# dnt_mko.net
KiCad netlist of a schematic drawn in Altium Designer
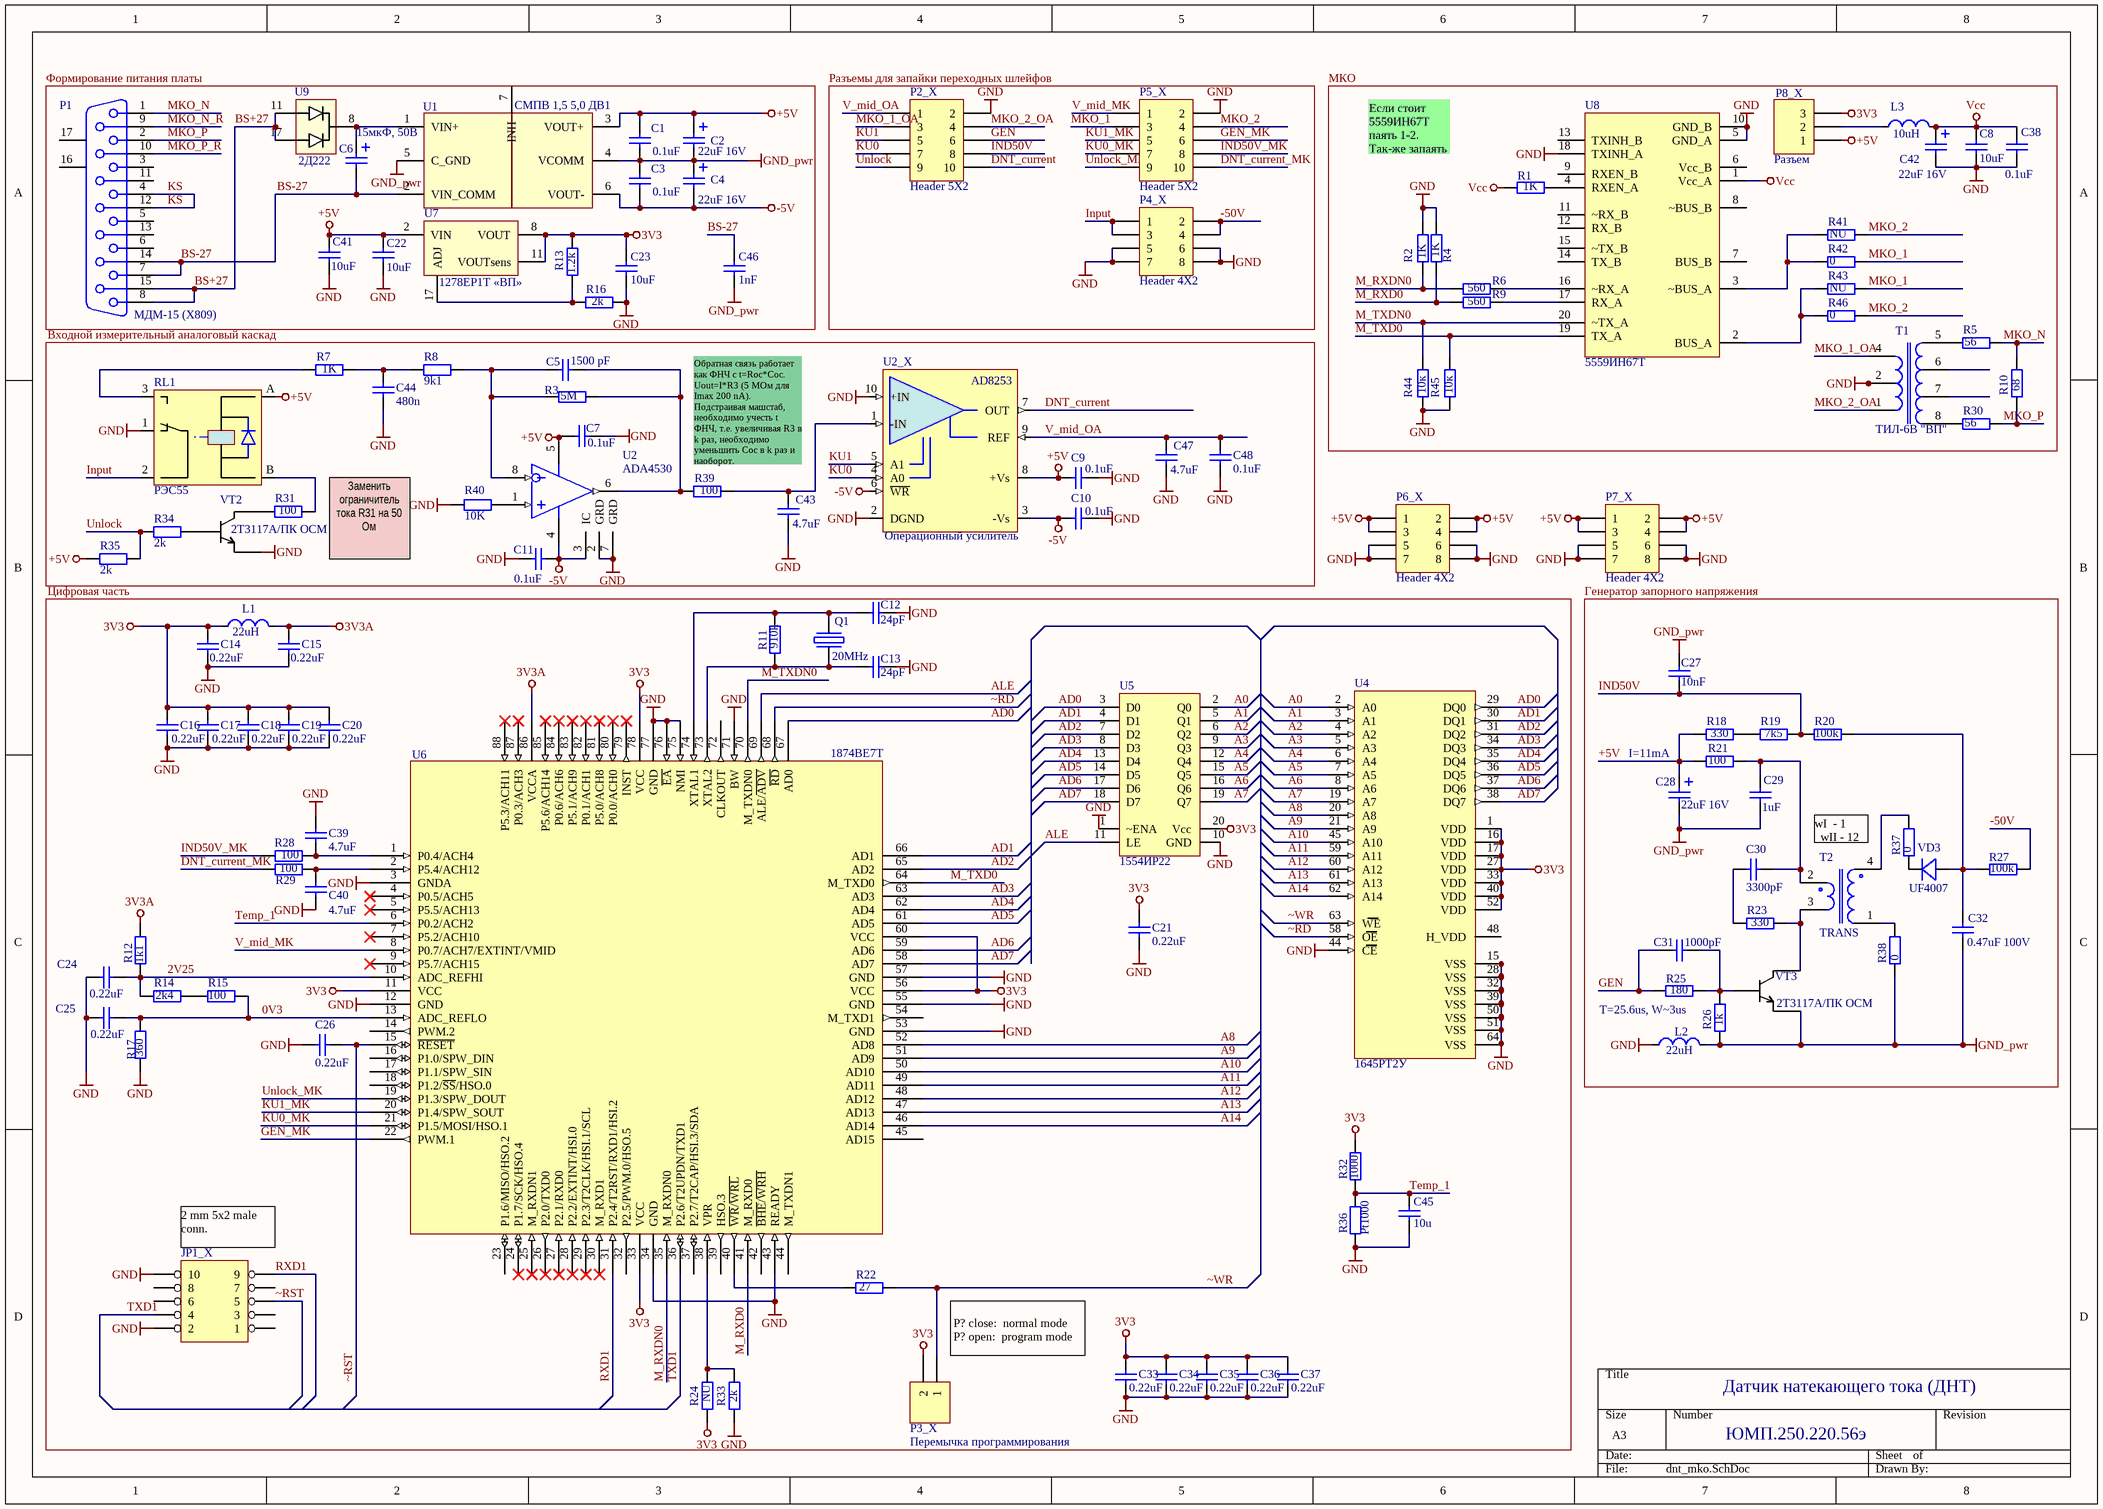
[diagram p0: dnt_mko.SchDoc]

(export (version "E")
  (design (tool "Eeschema 10.0.6"))
  (components
    (comp (ref "C1")
      (value "0.1uF")
      (footprint "CR-0805")
      (description "Capacitor")
      (fields (field (name "PUBLISHER") "Altium Limited"))
      (libsource (lib "MyLib") (part "C"))
    )
    (comp (ref "C2")
      (value "22uF 16V")
      (footprint "C_SMD_SIZE_B")
      (description "Capacitor")
      (fields (field (name "PUBLISHER") "Altium Limited"))
      (libsource (lib "MyLib") (part "C_pol"))
    )
    (comp (ref "C3")
      (value "0.1uF")
      (footprint "CR-0805")
      (description "Capacitor")
      (fields (field (name "PUBLISHER") "Altium Limited"))
      (libsource (lib "MyLib") (part "C"))
    )
    (comp (ref "C4")
      (value "22uF 16V")
      (footprint "C_SMD_SIZE_B")
      (description "Capacitor")
      (fields (field (name "PUBLISHER") "Altium Limited"))
      (libsource (lib "MyLib") (part "C_pol"))
    )
    (comp (ref "C5")
      (value "1500 pF")
      (footprint "CR-0805")
      (description "Capacitor")
      (fields (field (name "PUBLISHER") "Altium Limited"))
      (libsource (lib "MyLib") (part "C"))
    )
    (comp (ref "C6")
      (value "15мкФ, 50В")
      (footprint "C_SMD_size_D")
      (description "Capacitor")
      (fields (field (name "PUBLISHER") "Altium Limited"))
      (libsource (lib "MyLib") (part "C_pol"))
    )
    (comp (ref "C7")
      (value "0.1uF")
      (footprint "CR-0805")
      (description "Capacitor")
      (fields (field (name "PUBLISHER") "Altium Limited"))
      (libsource (lib "MyLib") (part "C"))
    )
    (comp (ref "C8")
      (value "10uF")
      (footprint "CR-0805")
      (description "Capacitor")
      (fields (field (name "PUBLISHER") "Altium Limited"))
      (libsource (lib "MyLib") (part "C"))
    )
    (comp (ref "C9")
      (value "0.1uF")
      (footprint "CR-0805")
      (description "Capacitor")
      (fields (field (name "PUBLISHER") "Altium Limited"))
      (libsource (lib "MyLib") (part "C"))
    )
    (comp (ref "C10")
      (value "0.1uF")
      (footprint "CR-0805")
      (description "Capacitor")
      (fields (field (name "PUBLISHER") "Altium Limited"))
      (libsource (lib "MyLib") (part "C"))
    )
    (comp (ref "C11")
      (value "0.1uF")
      (footprint "CR-0805")
      (description "Capacitor")
      (fields (field (name "PUBLISHER") "Altium Limited"))
      (libsource (lib "MyLib") (part "C"))
    )
    (comp (ref "C12")
      (value "24pF")
      (footprint "CR-0805")
      (description "Capacitor")
      (fields (field (name "PUBLISHER") "Altium Limited"))
      (libsource (lib "MyLib") (part "C"))
    )
    (comp (ref "C13")
      (value "24pF")
      (footprint "CR-0805")
      (description "Capacitor")
      (fields (field (name "PUBLISHER") "Altium Limited"))
      (libsource (lib "MyLib") (part "C"))
    )
    (comp (ref "C14")
      (value "0.22uF")
      (footprint "CR-0805")
      (description "Capacitor")
      (fields (field (name "PUBLISHER") "Altium Limited"))
      (libsource (lib "MyLib") (part "C"))
    )
    (comp (ref "C15")
      (value "0.22uF")
      (footprint "CR-0805")
      (description "Capacitor")
      (fields (field (name "PUBLISHER") "Altium Limited"))
      (libsource (lib "MyLib") (part "C"))
    )
    (comp (ref "C16")
      (value "0.22uF")
      (footprint "CR-0805")
      (description "Capacitor")
      (fields (field (name "PUBLISHER") "Altium Limited"))
      (libsource (lib "MyLib") (part "C"))
    )
    (comp (ref "C17")
      (value "0.22uF")
      (footprint "CR-0805")
      (description "Capacitor")
      (fields (field (name "PUBLISHER") "Altium Limited"))
      (libsource (lib "MyLib") (part "C"))
    )
    (comp (ref "C18")
      (value "0.22uF")
      (footprint "CR-0805")
      (description "Capacitor")
      (fields (field (name "PUBLISHER") "Altium Limited"))
      (libsource (lib "MyLib") (part "C"))
    )
    (comp (ref "C19")
      (value "0.22uF")
      (footprint "CR-0805")
      (description "Capacitor")
      (fields (field (name "PUBLISHER") "Altium Limited"))
      (libsource (lib "MyLib") (part "C"))
    )
    (comp (ref "C20")
      (value "0.22uF")
      (footprint "CR-0805")
      (description "Capacitor")
      (fields (field (name "PUBLISHER") "Altium Limited"))
      (libsource (lib "MyLib") (part "C"))
    )
    (comp (ref "C21")
      (value "0.22uF")
      (footprint "CR-0805")
      (description "Capacitor")
      (fields (field (name "PUBLISHER") "Altium Limited"))
      (libsource (lib "MyLib") (part "C"))
    )
    (comp (ref "C22")
      (value "10uF")
      (footprint "CR-0805")
      (description "Capacitor")
      (fields (field (name "PUBLISHER") "Altium Limited"))
      (libsource (lib "MyLib") (part "C"))
    )
    (comp (ref "C23")
      (value "10uF")
      (footprint "CR-0805")
      (description "Capacitor")
      (fields (field (name "PUBLISHER") "Altium Limited"))
      (libsource (lib "MyLib") (part "C"))
    )
    (comp (ref "C24")
      (value "0.22uF")
      (footprint "CR-0805")
      (description "Capacitor")
      (fields (field (name "PUBLISHER") "Altium Limited"))
      (libsource (lib "MyLib") (part "C"))
    )
    (comp (ref "C25")
      (value "0.22uF")
      (footprint "CR-0805")
      (description "Capacitor")
      (fields (field (name "PUBLISHER") "Altium Limited"))
      (libsource (lib "MyLib") (part "C"))
    )
    (comp (ref "C26")
      (value "0.22uF")
      (footprint "CR-0805")
      (description "Capacitor")
      (fields (field (name "PUBLISHER") "Altium Limited"))
      (libsource (lib "MyLib") (part "C"))
    )
    (comp (ref "C27")
      (value "10nF")
      (footprint "CR-0805")
      (description "Capacitor")
      (fields (field (name "PUBLISHER") "Altium Limited"))
      (libsource (lib "MyLib") (part "C"))
    )
    (comp (ref "C28")
      (value "22uF 16V")
      (footprint "C_SMD_SIZE_B")
      (description "Capacitor")
      (fields (field (name "PUBLISHER") "Altium Limited"))
      (libsource (lib "MyLib") (part "C_pol"))
    )
    (comp (ref "C29")
      (value "1uF")
      (footprint "CR-0805")
      (description "Capacitor")
      (fields (field (name "PUBLISHER") "Altium Limited"))
      (libsource (lib "MyLib") (part "C"))
    )
    (comp (ref "C30")
      (value "3300pF")
      (footprint "CR-0805")
      (description "Capacitor")
      (fields (field (name "PUBLISHER") "Altium Limited"))
      (libsource (lib "MyLib") (part "C"))
    )
    (comp (ref "C31")
      (value "1000pF")
      (footprint "CR-0805")
      (description "Capacitor")
      (fields (field (name "PUBLISHER") "Altium Limited"))
      (libsource (lib "MyLib") (part "C"))
    )
    (comp (ref "C32")
      (value "0.47uF 100V")
      (footprint "CR-0805")
      (description "Capacitor")
      (fields (field (name "PUBLISHER") "Altium Limited"))
      (libsource (lib "MyLib") (part "C"))
    )
    (comp (ref "C33")
      (value "0.22uF")
      (footprint "CR-0805")
      (description "Capacitor")
      (fields (field (name "PUBLISHER") "Altium Limited"))
      (libsource (lib "MyLib") (part "C"))
    )
    (comp (ref "C34")
      (value "0.22uF")
      (footprint "CR-0805")
      (description "Capacitor")
      (fields (field (name "PUBLISHER") "Altium Limited"))
      (libsource (lib "MyLib") (part "C"))
    )
    (comp (ref "C35")
      (value "0.22uF")
      (footprint "CR-0805")
      (description "Capacitor")
      (fields (field (name "PUBLISHER") "Altium Limited"))
      (libsource (lib "MyLib") (part "C"))
    )
    (comp (ref "C36")
      (value "0.22uF")
      (footprint "CR-0805")
      (description "Capacitor")
      (fields (field (name "PUBLISHER") "Altium Limited"))
      (libsource (lib "MyLib") (part "C"))
    )
    (comp (ref "C37")
      (value "0.22uF")
      (footprint "CR-0805")
      (description "Capacitor")
      (fields (field (name "PUBLISHER") "Altium Limited"))
      (libsource (lib "MyLib") (part "C"))
    )
    (comp (ref "C38")
      (value "0.1uF")
      (footprint "CR-0805")
      (description "Capacitor")
      (fields (field (name "PUBLISHER") "Altium Limited"))
      (libsource (lib "MyLib") (part "C"))
    )
    (comp (ref "C39")
      (value "4.7uF")
      (footprint "CR-0805")
      (description "Capacitor")
      (fields (field (name "PUBLISHER") "Altium Limited"))
      (libsource (lib "MyLib") (part "C"))
    )
    (comp (ref "C40")
      (value "4.7uF")
      (footprint "CR-0805")
      (description "Capacitor")
      (fields (field (name "PUBLISHER") "Altium Limited"))
      (libsource (lib "MyLib") (part "C"))
    )
    (comp (ref "C41")
      (value "10uF")
      (footprint "CR-0805")
      (description "Capacitor")
      (fields (field (name "PUBLISHER") "Altium Limited"))
      (libsource (lib "MyLib") (part "C"))
    )
    (comp (ref "C42")
      (value "22uF 16V")
      (footprint "C_SMD_SIZE_B")
      (description "Capacitor")
      (fields (field (name "PUBLISHER") "Altium Limited"))
      (libsource (lib "MyLib") (part "C_pol"))
    )
    (comp (ref "C43")
      (value "4.7uF")
      (footprint "CR-0805")
      (description "Capacitor")
      (fields (field (name "PUBLISHER") "Altium Limited"))
      (libsource (lib "MyLib") (part "C"))
    )
    (comp (ref "C44")
      (value "480n")
      (footprint "CR-0805")
      (description "Capacitor")
      (fields (field (name "PUBLISHER") "Altium Limited"))
      (libsource (lib "MyLib") (part "C"))
    )
    (comp (ref "C45")
      (value "10u")
      (footprint "CR-0805")
      (description "Capacitor")
      (fields (field (name "PUBLISHER") "Altium Limited"))
      (libsource (lib "MyLib") (part "C"))
    )
    (comp (ref "C46")
      (value "1nF")
      (footprint "CR-1206")
      (description "Capacitor")
      (fields (field (name "PUBLISHER") "Altium Limited"))
      (libsource (lib "MyLib") (part "C"))
    )
    (comp (ref "C47")
      (value "4.7uF")
      (footprint "CR-0805")
      (description "Capacitor")
      (fields (field (name "PUBLISHER") "Altium Limited"))
      (libsource (lib "MyLib") (part "C"))
    )
    (comp (ref "C48")
      (value "0.1uF")
      (footprint "CR-0805")
      (description "Capacitor")
      (fields (field (name "PUBLISHER") "Altium Limited"))
      (libsource (lib "MyLib") (part "C"))
    )
    (comp (ref "JP1_X") (value "~") (footprint "IDC2-10") (libsource (lib "*") (part "HEADER 5X2")))
    (comp (ref "L1")
      (value "22uH")
      (footprint "C_SMD_SIZE_B")
      (description "Inductor")
      (libsource (lib "*") (part "INDUCTOR"))
    )
    (comp (ref "L2")
      (value "22uH")
      (footprint "C_SMD_SIZE_B")
      (description "Inductor")
      (libsource (lib "*") (part "INDUCTOR"))
    )
    (comp (ref "L3")
      (value "10uH")
      (footprint "C_SMD_SIZE_B")
      (description "Inductor")
      (libsource (lib "*") (part "INDUCTOR"))
    )
    (comp (ref "P1")
      (value "MDM-15")
      (footprint "MDM-15")
      (description "Receptacle Assembly, 15 Position, Right Angle")
      (fields (field (name "НАИМЕНОВАНИЕ") "МДМ-15 (X809)"))
      (libsource (lib "Miscellaneous Connectors") (part "D Connector 15"))
    )
    (comp (ref "P2_X")
      (value "Header 5X2")
      (footprint "IDC2-10")
      (description "Header, 5-Pin, Dual row")
      (fields (field (name "PUBLISHER") "Altium Limited"))
      (libsource (lib "Miscellaneous Connectors") (part "Header 5X2"))
    )
    (comp (ref "P3_X")
      (value "Перемычка программирования")
      (footprint "IDC2-2")
      (description "Header, 2-Pin")
      (libsource (lib "Miscellaneous Connectors") (part "Header 2"))
    )
    (comp (ref "P4_X")
      (value "Header 4X2")
      (footprint "IDC2-8")
      (description "Header, 4-Pin, Dual row")
      (fields (field (name "PUBLISHER") "Altium Limited"))
      (libsource (lib "Miscellaneous Connectors") (part "Header 4X2"))
    )
    (comp (ref "P5_X")
      (value "Header 5X2")
      (footprint "IDC2-10")
      (description "Header, 5-Pin, Dual row")
      (fields (field (name "PUBLISHER") "Altium Limited"))
      (libsource (lib "Miscellaneous Connectors") (part "Header 5X2"))
    )
    (comp (ref "P6_X")
      (value "Header 4X2")
      (footprint "IDC2-8")
      (description "Header, 4-Pin, Dual row")
      (fields (field (name "PUBLISHER") "Altium Limited"))
      (libsource (lib "Miscellaneous Connectors") (part "Header 4X2"))
    )
    (comp (ref "P7_X")
      (value "Header 4X2")
      (footprint "IDC2-8")
      (description "Header, 4-Pin, Dual row")
      (fields (field (name "PUBLISHER") "Altium Limited"))
      (libsource (lib "Miscellaneous Connectors") (part "Header 4X2"))
    )
    (comp (ref "P8_X")
      (value "Разъем")
      (footprint "IDC2-3")
      (description "Header, 3-Pin")
      (fields (field (name "PUBLISHER") "Altium Limited"))
      (libsource (lib "Miscellaneous Connectors") (part "Header 3"))
    )
    (comp (ref "Q1")
      (value "20MHz")
      (footprint "RK-386MM")
      (description "Resonator")
      (libsource (lib "*") (part "QUARZ"))
    )
    (comp (ref "R1")
      (value "1K")
      (footprint "CR-0805")
      (description "Resistor")
      (fields (field (name "PUBLISHER") "Altium Limited"))
      (libsource (lib "MyLib") (part "R"))
    )
    (comp (ref "R2")
      (value "1K")
      (footprint "CR-0805")
      (description "Resistor")
      (fields (field (name "PUBLISHER") "Altium Limited"))
      (libsource (lib "") (part "R_2"))
    )
    (comp (ref "R3")
      (value "5M")
      (footprint "CR-1206")
      (description "Resistor")
      (libsource (lib "") (part "R_1"))
    )
    (comp (ref "R4")
      (value "1K")
      (footprint "CR-0805")
      (description "Resistor")
      (fields (field (name "PUBLISHER") "Altium Limited"))
      (libsource (lib "") (part "R_2"))
    )
    (comp (ref "R5")
      (value "56")
      (footprint "CR-1206")
      (description "Resistor")
      (fields (field (name "PUBLISHER") "Altium Limited"))
      (libsource (lib "") (part "R_1"))
    )
    (comp (ref "R6")
      (value "560")
      (footprint "CR-0805")
      (description "Resistor")
      (fields (field (name "PUBLISHER") "Altium Limited"))
      (libsource (lib "") (part "R_1"))
    )
    (comp (ref "R7")
      (value "1K")
      (footprint "CR-0805")
      (description "Resistor")
      (fields (field (name "PUBLISHER") "Altium Limited"))
      (libsource (lib "MyLib") (part "R"))
    )
    (comp (ref "R8")
      (value "9k1")
      (footprint "CR-0805")
      (description "Resistor")
      (fields (field (name "PUBLISHER") "Altium Limited"))
      (libsource (lib "") (part "R_1"))
    )
    (comp (ref "R9")
      (value "560")
      (footprint "CR-0805")
      (description "Resistor")
      (fields (field (name "PUBLISHER") "Altium Limited"))
      (libsource (lib "") (part "R_1"))
    )
    (comp (ref "R10")
      (value "68")
      (footprint "CR-1206")
      (description "Resistor")
      (fields (field (name "PUBLISHER") "Altium Limited"))
      (libsource (lib "") (part "R_3"))
    )
    (comp (ref "R11")
      (value "910k")
      (footprint "CR-0805")
      (description "Resistor")
      (fields (field (name "PUBLISHER") "Altium Limited"))
      (libsource (lib "") (part "R_3"))
    )
    (comp (ref "R12")
      (value "1k1")
      (footprint "CR-0805")
      (description "Resistor")
      (fields (field (name "PUBLISHER") "Altium Limited"))
      (libsource (lib "") (part "R_2"))
    )
    (comp (ref "R13")
      (value "1.2k")
      (footprint "CR-0805")
      (description "Resistor")
      (fields (field (name "PUBLISHER") "Altium Limited"))
      (libsource (lib "") (part "R_2"))
    )
    (comp (ref "R14")
      (value "2k4")
      (footprint "CR-0805")
      (description "Resistor")
      (fields (field (name "PUBLISHER") "Altium Limited"))
      (libsource (lib "") (part "R_1"))
    )
    (comp (ref "R15")
      (value "100")
      (footprint "CR-0805")
      (description "Resistor")
      (fields (field (name "PUBLISHER") "Altium Limited"))
      (libsource (lib "") (part "R_1"))
    )
    (comp (ref "R16")
      (value "2k")
      (footprint "CR-0805")
      (description "Resistor")
      (fields (field (name "PUBLISHER") "Altium Limited"))
      (libsource (lib "MyLib") (part "R"))
    )
    (comp (ref "R17")
      (value "360")
      (footprint "CR-0805")
      (description "Resistor")
      (fields (field (name "PUBLISHER") "Altium Limited"))
      (libsource (lib "") (part "R_2"))
    )
    (comp (ref "R18")
      (value "330")
      (footprint "CR-0805")
      (description "Resistor")
      (fields (field (name "PUBLISHER") "Altium Limited"))
      (libsource (lib "") (part "R_1"))
    )
    (comp (ref "R19")
      (value "7k5")
      (footprint "CR-0805")
      (description "Resistor")
      (fields (field (name "PUBLISHER") "Altium Limited"))
      (libsource (lib "") (part "R_1"))
    )
    (comp (ref "R20")
      (value "100k")
      (footprint "CR-0805")
      (description "Resistor")
      (fields (field (name "PUBLISHER") "Altium Limited"))
      (libsource (lib "") (part "R_1"))
    )
    (comp (ref "R21")
      (value "100")
      (footprint "CR-0805")
      (description "Resistor")
      (fields (field (name "PUBLISHER") "Altium Limited"))
      (libsource (lib "") (part "R_1"))
    )
    (comp (ref "R22")
      (value "27")
      (footprint "CR-0805")
      (description "Resistor")
      (fields (field (name "PUBLISHER") "Altium Limited"))
      (libsource (lib "") (part "R_1"))
    )
    (comp (ref "R23")
      (value "330")
      (footprint "CR-0805")
      (description "Resistor")
      (fields (field (name "PUBLISHER") "Altium Limited"))
      (libsource (lib "") (part "R_1"))
    )
    (comp (ref "R24")
      (value "NU")
      (footprint "CR-0805")
      (description "Resistor")
      (fields (field (name "PUBLISHER") "Altium Limited"))
      (libsource (lib "") (part "R_3"))
    )
    (comp (ref "R25")
      (value "180")
      (footprint "CR-0805")
      (description "Resistor")
      (fields (field (name "PUBLISHER") "Altium Limited"))
      (libsource (lib "") (part "R_1"))
    )
    (comp (ref "R26")
      (value "1k")
      (footprint "CR-0805")
      (description "Resistor")
      (fields (field (name "PUBLISHER") "Altium Limited"))
      (libsource (lib "") (part "R_3"))
    )
    (comp (ref "R27")
      (value "100k")
      (footprint "CR-0805")
      (description "Resistor")
      (fields (field (name "PUBLISHER") "Altium Limited"))
      (libsource (lib "MyLib") (part "R"))
    )
    (comp (ref "R28")
      (value "100")
      (footprint "CR-0805")
      (description "Resistor")
      (fields (field (name "PUBLISHER") "Altium Limited"))
      (libsource (lib "") (part "R_1"))
    )
    (comp (ref "R29")
      (value "100")
      (footprint "CR-0805")
      (description "Resistor")
      (fields (field (name "PUBLISHER") "Altium Limited"))
      (libsource (lib "") (part "R_1"))
    )
    (comp (ref "R30")
      (value "56")
      (footprint "CR-1206")
      (description "Resistor")
      (fields (field (name "PUBLISHER") "Altium Limited"))
      (libsource (lib "") (part "R_1"))
    )
    (comp (ref "R31")
      (value "100")
      (footprint "CR-0805")
      (description "Resistor")
      (fields (field (name "PUBLISHER") "Altium Limited"))
      (libsource (lib "MyLib") (part "R"))
    )
    (comp (ref "R32")
      (value "1000")
      (footprint "CR-0805")
      (description "Resistor")
      (fields (field (name "PUBLISHER") "Altium Limited"))
      (libsource (lib "") (part "R_3"))
    )
    (comp (ref "R33")
      (value "2k")
      (footprint "CR-0805")
      (description "Resistor")
      (fields (field (name "PUBLISHER") "Altium Limited"))
      (libsource (lib "") (part "R_3"))
    )
    (comp (ref "R34")
      (value "2k")
      (footprint "CR-0805")
      (description "Resistor")
      (fields (field (name "PUBLISHER") "Altium Limited"))
      (libsource (lib "MyLib") (part "R"))
    )
    (comp (ref "R35")
      (value "2k")
      (footprint "CR-0805")
      (description "Resistor")
      (fields (field (name "PUBLISHER") "Altium Limited"))
      (libsource (lib "") (part "R_1"))
    )
    (comp (ref "R36")
      (value "Pt1000")
      (footprint "Pt100")
      (description "Resistor")
      (fields (field (name "PUBLISHER") "Altium Limited"))
      (libsource (lib "") (part "R_3"))
    )
    (comp (ref "R37")
      (value "0")
      (footprint "CR-0805")
      (description "Resistor")
      (fields (field (name "PUBLISHER") "Altium Limited"))
      (libsource (lib "") (part "R_3"))
    )
    (comp (ref "R38")
      (value "0")
      (footprint "CR-0805")
      (description "Resistor")
      (fields (field (name "PUBLISHER") "Altium Limited"))
      (libsource (lib "") (part "R_3"))
    )
    (comp (ref "R39")
      (value "100")
      (footprint "CR-0805")
      (description "Resistor")
      (fields (field (name "PUBLISHER") "Altium Limited"))
      (libsource (lib "MyLib") (part "R"))
    )
    (comp (ref "R40")
      (value "10K")
      (footprint "CR-0805")
      (description "Resistor")
      (fields (field (name "PUBLISHER") "Altium Limited"))
      (libsource (lib "MyLib") (part "R"))
    )
    (comp (ref "R41")
      (value "NU")
      (footprint "CR-0805")
      (description "Resistor")
      (fields (field (name "PUBLISHER") "Altium Limited"))
      (libsource (lib "") (part "R_1"))
    )
    (comp (ref "R42")
      (value "0")
      (footprint "CR-0805")
      (description "Resistor")
      (fields (field (name "PUBLISHER") "Altium Limited"))
      (libsource (lib "") (part "R_1"))
    )
    (comp (ref "R43")
      (value "NU")
      (footprint "CR-0805")
      (description "Resistor")
      (fields (field (name "PUBLISHER") "Altium Limited"))
      (libsource (lib "") (part "R_1"))
    )
    (comp (ref "R44")
      (value "10к")
      (footprint "CR-0805")
      (description "Resistor")
      (fields (field (name "PUBLISHER") "Altium Limited"))
      (libsource (lib "") (part "R_2"))
    )
    (comp (ref "R45")
      (value "10к")
      (footprint "CR-0805")
      (description "Resistor")
      (fields (field (name "PUBLISHER") "Altium Limited"))
      (libsource (lib "") (part "R_2"))
    )
    (comp (ref "R46")
      (value "0")
      (footprint "CR-0805")
      (description "Resistor")
      (fields (field (name "PUBLISHER") "Altium Limited"))
      (libsource (lib "") (part "R_1"))
    )
    (comp (ref "RL1")
      (value "РЭС55")
      (footprint "MyLib_1:РЭС55")
      (description "Реле")
      (libsource (lib "MyLib") (part "RGK-56"))
    )
    (comp (ref "T1")
      (value "ТИЛ-6В \"ВП\"")
      (footprint "ТИЛ6В")
      (description "Transformator")
      (libsource (lib "*") (part "TIL6B"))
    )
    (comp (ref "T2")
      (value "TRANS")
      (footprint "TRANS 50V")
      (description "Transformer")
      (libsource (lib "My_lib_1") (part "TRANS"))
    )
    (comp (ref "U1")
      (value "СМПВ 1,5 5,0 ДВ1")
      (footprint "SLH 2805")
      (libsource (lib "My_lib_1") (part "SLH2805"))
    )
    (comp (ref "U2")
      (value "ADA4530")
      (footprint "MyLib:SO-8")
      (description "Ultra-Low Bias Current Difet OpAmp")
      (libsource (lib "My_lib_1") (part "ADA4530"))
    )
    (comp (ref "U2_X")
      (value "AD8253")
      (footprint "u_SO-10")
      (description "10 MHz, 20 V/мs, G = 1, 2, 4, 8 iCMOS Programmable Gain Instrumentation Amplifier")
      (fields (field (name "НАЗНАЧЕНИЕ") "Операционный усилитель") (field (name "НАИМЕНОВАНИЕ") "AD8253"))
      (libsource (lib "MyLib") (part "AD8251"))
    )
    (comp (ref "U4")
      (value "1645РТ2У")
      (footprint "5134.64-6")
      (libsource (lib "My_lib_1") (part "1645РТ2У"))
    )
    (comp (ref "U5")
      (value "1554ИР22")
      (footprint "20PIN FLATPACK")
      (libsource (lib "My_lib_1") (part "1554ИР22"))
    )
    (comp (ref "U6")
      (value "1874BE7T")
      (footprint "4235.88-1")
      (description "Microcontroller")
      (libsource (lib "*") (part "1874BE7T"))
    )
    (comp (ref "U7")
      (value "1278ЕР1Т «ВП»")
      (footprint "1278ЕР1Т - БУ")
      (libsource (lib "My_lib_1") (part "1278ER1T VP"))
    )
    (comp (ref "U8")
      (value "5559ИН67Т")
      (footprint "20PIN FLATPACK")
      (libsource (lib "My_lib_1") (part "5559ИН67Т"))
    )
    (comp (ref "U9")
      (value "2D222")
      (footprint "1278ЕР1Т - БУ")
      (fields (field (name "НАИМЕНОВАНИЕ") "2Д222"))
      (libsource (lib "My_lib_1") (part "2D222"))
    )
    (comp (ref "VD3")
      (value "UF4007")
      (footprint "AXIAL-0.4")
      (description "Diode")
      (libsource (lib "*") (part "DIODE"))
    )
    (comp (ref "VT2")
      (value "2Т3117А/ПК ОСМ")
      (footprint "2Д3117А")
      (libsource (lib "My_lib_1") (part "2T3117A"))
    )
    (comp (ref "VT3")
      (value "2Т3117А/ПК ОСМ")
      (footprint "2Д3117А")
      (libsource (lib "My_lib_1") (part "2T3117A"))
    )
  )
  (nets
    (net (code "1") (name "+5V") (class "Default")
      (node (ref "C1") (pin "2") (pinfunction "2_2") (pintype "passive"))
      (node (ref "C2") (pin "1") (pinfunction "1_1") (pintype "passive"))
      (node (ref "C22") (pin "1") (pinfunction "1_1") (pintype "passive"))
      (node (ref "C28") (pin "1") (pinfunction "1_1") (pintype "passive"))
      (node (ref "C41") (pin "1") (pinfunction "1_1") (pintype "passive"))
      (node (ref "C7") (pin "1") (pinfunction "1_1") (pintype "passive"))
      (node (ref "C9") (pin "1") (pinfunction "1_1") (pintype "passive"))
      (node (ref "P6_X") (pin "1") (pinfunction "1_1") (pintype "passive"))
      (node (ref "P6_X") (pin "2") (pinfunction "2_2") (pintype "passive"))
      (node (ref "P6_X") (pin "3") (pinfunction "3_3") (pintype "passive"))
      (node (ref "P6_X") (pin "4") (pinfunction "4_4") (pintype "passive"))
      (node (ref "P7_X") (pin "1") (pinfunction "1_1") (pintype "passive"))
      (node (ref "P7_X") (pin "2") (pinfunction "2_2") (pintype "passive"))
      (node (ref "P7_X") (pin "3") (pinfunction "3_3") (pintype "passive"))
      (node (ref "P7_X") (pin "4") (pinfunction "4_4") (pintype "passive"))
      (node (ref "P8_X") (pin "1") (pinfunction "1_1") (pintype "passive"))
      (node (ref "R18") (pin "1") (pinfunction "1_1") (pintype "passive"))
      (node (ref "R21") (pin "1") (pinfunction "1_1") (pintype "passive"))
      (node (ref "R35") (pin "1") (pinfunction "1_1") (pintype "passive"))
      (node (ref "RL1") (pin "A") (pintype "passive"))
      (node (ref "U1") (pin "3") (pinfunction "VOUT+_3") (pintype "passive"))
      (node (ref "U2") (pin "5") (pinfunction "V+_5") (pintype "power_in"))
      (node (ref "U2_X") (pin "8") (pinfunction "+Vs_8") (pintype "power_in"))
      (node (ref "U7") (pin "2") (pinfunction "VIN_2") (pintype "passive"))
    )
    (net (code "2") (name "-5V") (class "Default")
      (node (ref "C10") (pin "1") (pinfunction "1_1") (pintype "passive"))
      (node (ref "C11") (pin "2") (pinfunction "2_2") (pintype "passive"))
      (node (ref "C3") (pin "1") (pinfunction "1_1") (pintype "passive"))
      (node (ref "C4") (pin "2") (pinfunction "2_2") (pintype "passive"))
      (node (ref "U1") (pin "6") (pinfunction "VOUT-_6") (pintype "passive"))
      (node (ref "U2") (pin "3") (pinfunction "IC_3") (pintype "passive"))
      (node (ref "U2") (pin "4") (pinfunction "V-_4") (pintype "power_in"))
      (node (ref "U2_X") (pin "3") (pinfunction "-Vs_3") (pintype "power_in"))
      (node (ref "U2_X") (pin "6") (pinfunction "~{WR}_6") (pintype "input"))
    )
    (net (code "3") (name "/-50V") (class "Default")
      (node (ref "P4_X") (pin "2") (pinfunction "2_2") (pintype "passive"))
      (node (ref "P4_X") (pin "4") (pinfunction "4_4") (pintype "passive"))
      (node (ref "R27") (pin "1") (pinfunction "1_1") (pintype "passive"))
    )
    (net (code "4") (name "/0V3") (class "Default")
      (node (ref "C25") (pin "1") (pinfunction "1_1") (pintype "passive"))
      (node (ref "R15") (pin "2") (pinfunction "2_2") (pintype "passive"))
      (node (ref "R17") (pin "1") (pinfunction "1_1") (pintype "passive"))
      (node (ref "U6") (pin "13") (pinfunction "ADC_REFLO_13") (pintype "input"))
    )
    (net (code "5") (name "/2V25") (class "Default")
      (node (ref "C24") (pin "1") (pinfunction "1_1") (pintype "passive"))
      (node (ref "R12") (pin "2") (pinfunction "2_2") (pintype "passive"))
      (node (ref "R14") (pin "1") (pinfunction "1_1") (pintype "passive"))
      (node (ref "U6") (pin "10") (pinfunction "ADC_REFHI_10") (pintype "input"))
    )
    (net (code "6") (name "/A0") (class "Default")
      (node (ref "U4") (pin "2") (pinfunction "A0_2") (pintype "input"))
      (node (ref "U5") (pin "2") (pinfunction "Q0_2") (pintype "passive"))
    )
    (net (code "7") (name "/A1") (class "Default")
      (node (ref "U4") (pin "3") (pinfunction "A1_3") (pintype "input"))
      (node (ref "U5") (pin "5") (pinfunction "Q1_5") (pintype "passive"))
    )
    (net (code "8") (name "/A2") (class "Default")
      (node (ref "U4") (pin "4") (pinfunction "A2_4") (pintype "input"))
      (node (ref "U5") (pin "6") (pinfunction "Q2_6") (pintype "passive"))
    )
    (net (code "9") (name "/A3") (class "Default")
      (node (ref "U4") (pin "5") (pinfunction "A3_5") (pintype "input"))
      (node (ref "U5") (pin "9") (pinfunction "Q3_9") (pintype "passive"))
    )
    (net (code "10") (name "/A4") (class "Default")
      (node (ref "U4") (pin "6") (pinfunction "A4_6") (pintype "input"))
      (node (ref "U5") (pin "12") (pinfunction "Q4_12") (pintype "passive"))
    )
    (net (code "11") (name "/A5") (class "Default")
      (node (ref "U4") (pin "7") (pinfunction "A5_7") (pintype "input"))
      (node (ref "U5") (pin "15") (pinfunction "Q5_15") (pintype "passive"))
    )
    (net (code "12") (name "/A6") (class "Default")
      (node (ref "U4") (pin "8") (pinfunction "A6_8") (pintype "input"))
      (node (ref "U5") (pin "16") (pinfunction "Q6_16") (pintype "passive"))
    )
    (net (code "13") (name "/A7") (class "Default")
      (node (ref "U4") (pin "19") (pinfunction "A7_19") (pintype "input"))
      (node (ref "U5") (pin "19") (pinfunction "Q7_19") (pintype "passive"))
    )
    (net (code "14") (name "/A8") (class "Default")
      (node (ref "U4") (pin "20") (pinfunction "A8_20") (pintype "input"))
      (node (ref "U6") (pin "52") (pinfunction "AD8_52") (pintype "tri_state"))
    )
    (net (code "15") (name "/A9") (class "Default")
      (node (ref "U4") (pin "21") (pinfunction "A9_21") (pintype "input"))
      (node (ref "U6") (pin "51") (pinfunction "AD9_51") (pintype "tri_state"))
    )
    (net (code "16") (name "/A10") (class "Default")
      (node (ref "U4") (pin "45") (pinfunction "A10_45") (pintype "input"))
      (node (ref "U6") (pin "50") (pinfunction "AD10_50") (pintype "tri_state"))
    )
    (net (code "17") (name "/A11") (class "Default")
      (node (ref "U4") (pin "59") (pinfunction "A11_59") (pintype "input"))
      (node (ref "U6") (pin "49") (pinfunction "AD11_49") (pintype "tri_state"))
    )
    (net (code "18") (name "/A12") (class "Default")
      (node (ref "U4") (pin "60") (pinfunction "A12_60") (pintype "input"))
      (node (ref "U6") (pin "48") (pinfunction "AD12_48") (pintype "tri_state"))
    )
    (net (code "19") (name "/A13") (class "Default")
      (node (ref "U4") (pin "61") (pinfunction "A13_61") (pintype "input"))
      (node (ref "U6") (pin "47") (pinfunction "AD13_47") (pintype "tri_state"))
    )
    (net (code "20") (name "/A14") (class "Default")
      (node (ref "U4") (pin "62") (pinfunction "A14_62") (pintype "input"))
      (node (ref "U6") (pin "46") (pinfunction "AD14_46") (pintype "tri_state"))
    )
    (net (code "21") (name "/AD0") (class "Default")
      (node (ref "U4") (pin "29") (pinfunction "DQ0_29") (pintype "output"))
      (node (ref "U5") (pin "3") (pinfunction "D0_3") (pintype "passive"))
      (node (ref "U6") (pin "67") (pinfunction "AD0_67") (pintype "tri_state"))
    )
    (net (code "22") (name "/AD1") (class "Default")
      (node (ref "U4") (pin "30") (pinfunction "DQ1_30") (pintype "output"))
      (node (ref "U5") (pin "4") (pinfunction "D1_4") (pintype "passive"))
      (node (ref "U6") (pin "66") (pinfunction "AD1_66") (pintype "tri_state"))
    )
    (net (code "23") (name "/AD2") (class "Default")
      (node (ref "U4") (pin "31") (pinfunction "DQ2_31") (pintype "output"))
      (node (ref "U5") (pin "7") (pinfunction "D2_7") (pintype "passive"))
      (node (ref "U6") (pin "65") (pinfunction "AD2_65") (pintype "tri_state"))
    )
    (net (code "24") (name "/AD3") (class "Default")
      (node (ref "U4") (pin "34") (pinfunction "DQ3_34") (pintype "output"))
      (node (ref "U5") (pin "8") (pinfunction "D3_8") (pintype "passive"))
      (node (ref "U6") (pin "63") (pinfunction "AD3_63") (pintype "tri_state"))
    )
    (net (code "25") (name "/AD4") (class "Default")
      (node (ref "U4") (pin "35") (pinfunction "DQ4_35") (pintype "output"))
      (node (ref "U5") (pin "13") (pinfunction "D4_13") (pintype "passive"))
      (node (ref "U6") (pin "62") (pinfunction "AD4_62") (pintype "tri_state"))
    )
    (net (code "26") (name "/AD5") (class "Default")
      (node (ref "U4") (pin "36") (pinfunction "DQ5_36") (pintype "output"))
      (node (ref "U5") (pin "14") (pinfunction "D5_14") (pintype "passive"))
      (node (ref "U6") (pin "61") (pinfunction "AD5_61") (pintype "tri_state"))
    )
    (net (code "27") (name "/AD6") (class "Default")
      (node (ref "U4") (pin "37") (pinfunction "DQ6_37") (pintype "output"))
      (node (ref "U5") (pin "17") (pinfunction "D6_17") (pintype "passive"))
      (node (ref "U6") (pin "59") (pinfunction "AD6_59") (pintype "tri_state"))
    )
    (net (code "28") (name "/AD7") (class "Default")
      (node (ref "U4") (pin "38") (pinfunction "DQ7_38") (pintype "output"))
      (node (ref "U5") (pin "18") (pinfunction "D7_18") (pintype "passive"))
      (node (ref "U6") (pin "58") (pinfunction "AD7_58") (pintype "tri_state"))
    )
    (net (code "29") (name "/ALE") (class "Default")
      (node (ref "U5") (pin "11") (pinfunction "LE_11") (pintype "passive"))
      (node (ref "U6") (pin "69") (pinfunction "ALE/~{ADV}_69") (pintype "output"))
    )
    (net (code "30") (name "/BS+27") (class "Default")
      (node (ref "P1") (pin "15") (pinfunction "15_15") (pintype "passive"))
      (node (ref "P1") (pin "8") (pinfunction "8_8") (pintype "passive"))
      (node (ref "U9") (pin "11") (pintype "passive"))
      (node (ref "U9") (pin "17") (pintype "passive"))
    )
    (net (code "31") (name "/BS-27") (class "Default")
      (node (ref "C46") (pin "1") (pinfunction "1_1") (pintype "passive"))
      (node (ref "C6") (pin "2") (pinfunction "2_2") (pintype "passive"))
      (node (ref "P1") (pin "14") (pinfunction "14_14") (pintype "passive"))
      (node (ref "P1") (pin "7") (pinfunction "7_7") (pintype "passive"))
      (node (ref "U1") (pin "2") (pinfunction "VIN_COMM_2") (pintype "passive"))
    )
    (net (code "32") (name "/DNT_current") (class "Default")
      (node (ref "P2_X") (pin "10") (pinfunction "10_10") (pintype "passive"))
      (node (ref "U2_X") (pin "7") (pinfunction "OUT_7") (pintype "output"))
    )
    (net (code "33") (name "/DNT_current_MK") (class "Default")
      (node (ref "P5_X") (pin "10") (pinfunction "10_10") (pintype "passive"))
      (node (ref "R29") (pin "1") (pinfunction "1_1") (pintype "passive"))
    )
    (net (code "34") (name "/GEN") (class "Default")
      (node (ref "C31") (pin "2") (pinfunction "2_2") (pintype "passive"))
      (node (ref "P2_X") (pin "6") (pinfunction "6_6") (pintype "passive"))
      (node (ref "R25") (pin "1") (pinfunction "1_1") (pintype "passive"))
    )
    (net (code "35") (name "/GEN_MK") (class "Default")
      (node (ref "P5_X") (pin "6") (pinfunction "6_6") (pintype "passive"))
      (node (ref "U6") (pin "22") (pinfunction "PWM.1_22") (pintype "output"))
    )
    (net (code "36") (name "/IND50V") (class "Default")
      (node (ref "C27") (pin "2") (pinfunction "2_2") (pintype "passive"))
      (node (ref "P2_X") (pin "8") (pinfunction "8_8") (pintype "passive"))
      (node (ref "R19") (pin "2") (pinfunction "2_2") (pintype "passive"))
      (node (ref "R20") (pin "1") (pinfunction "1_1") (pintype "passive"))
    )
    (net (code "37") (name "/IND50V_MK") (class "Default")
      (node (ref "P5_X") (pin "8") (pinfunction "8_8") (pintype "passive"))
      (node (ref "R28") (pin "1") (pinfunction "1_1") (pintype "passive"))
    )
    (net (code "38") (name "/Input") (class "Default")
      (node (ref "P4_X") (pin "1") (pinfunction "1_1") (pintype "passive"))
      (node (ref "P4_X") (pin "3") (pinfunction "3_3") (pintype "passive"))
      (node (ref "RL1") (pin "2") (pinfunction "2_2") (pintype "passive"))
    )
    (net (code "39") (name "/KS") (class "Default")
      (node (ref "P1") (pin "12") (pinfunction "12_12") (pintype "passive"))
      (node (ref "P1") (pin "4") (pinfunction "4_4") (pintype "passive"))
    )
    (net (code "40") (name "/KU0") (class "Default")
      (node (ref "P2_X") (pin "7") (pinfunction "7_7") (pintype "passive"))
      (node (ref "U2_X") (pin "4") (pinfunction "A0_4") (pintype "input"))
    )
    (net (code "41") (name "/KU0_MK") (class "Default")
      (node (ref "P5_X") (pin "7") (pinfunction "7_7") (pintype "passive"))
      (node (ref "U6") (pin "21") (pinfunction "P1.5/MOSI/HSO.1_21") (pintype "bidirectional"))
    )
    (net (code "42") (name "/KU1") (class "Default")
      (node (ref "P2_X") (pin "5") (pinfunction "5_5") (pintype "passive"))
      (node (ref "U2_X") (pin "5") (pinfunction "A1_5") (pintype "input"))
    )
    (net (code "43") (name "/KU1_MK") (class "Default")
      (node (ref "P5_X") (pin "5") (pinfunction "5_5") (pintype "passive"))
      (node (ref "U6") (pin "20") (pinfunction "P1.4/SPW_SOUT_20") (pintype "bidirectional"))
    )
    (net (code "44") (name "/MKO_1") (class "Default")
      (node (ref "P5_X") (pin "3") (pinfunction "3_3") (pintype "passive"))
      (node (ref "R42") (pin "2") (pinfunction "2_2") (pintype "passive"))
      (node (ref "R43") (pin "2") (pinfunction "2_2") (pintype "passive"))
    )
    (net (code "45") (name "/MKO_1_OA") (class "Default")
      (node (ref "P2_X") (pin "3") (pinfunction "3_3") (pintype "passive"))
      (node (ref "T1") (pin "4") (pinfunction "4_4") (pintype "passive"))
    )
    (net (code "46") (name "/MKO_2") (class "Default")
      (node (ref "P5_X") (pin "4") (pinfunction "4_4") (pintype "passive"))
      (node (ref "R41") (pin "2") (pinfunction "2_2") (pintype "passive"))
      (node (ref "R46") (pin "2") (pinfunction "2_2") (pintype "passive"))
    )
    (net (code "47") (name "/MKO_2_OA") (class "Default")
      (node (ref "P2_X") (pin "4") (pinfunction "4_4") (pintype "passive"))
      (node (ref "T1") (pin "1") (pinfunction "1_1") (pintype "passive"))
    )
    (net (code "48") (name "/MKO_N") (class "Default")
      (node (ref "P1") (pin "1") (pinfunction "1_1") (pintype "passive"))
      (node (ref "R10") (pin "2") (pinfunction "2_2") (pintype "passive"))
      (node (ref "R5") (pin "2") (pinfunction "2_2") (pintype "passive"))
    )
    (net (code "49") (name "/MKO_N_R") (class "Default")
      (node (ref "P1") (pin "9") (pinfunction "9_9") (pintype "passive"))
    )
    (net (code "50") (name "/MKO_P") (class "Default")
      (node (ref "P1") (pin "2") (pinfunction "2_2") (pintype "passive"))
      (node (ref "R10") (pin "1") (pinfunction "1_1") (pintype "passive"))
      (node (ref "R30") (pin "2") (pinfunction "2_2") (pintype "passive"))
    )
    (net (code "51") (name "/MKO_P_R") (class "Default")
      (node (ref "P1") (pin "10") (pinfunction "10_10") (pintype "passive"))
    )
    (net (code "52") (name "/M_RXD0") (class "Default")
      (node (ref "R4") (pin "2") (pinfunction "2_2") (pintype "passive"))
      (node (ref "R9") (pin "1") (pinfunction "1_1") (pintype "passive"))
      (node (ref "U6") (pin "41") (pinfunction "M_RXD0_41") (pintype "input"))
    )
    (net (code "53") (name "/M_RXDN0") (class "Default")
      (node (ref "R2") (pin "2") (pinfunction "2_2") (pintype "passive"))
      (node (ref "R6") (pin "1") (pinfunction "1_1") (pintype "passive"))
      (node (ref "U6") (pin "35") (pinfunction "M_RXDN0_35") (pintype "input"))
    )
    (net (code "54") (name "/M_TXD0") (class "Default")
      (node (ref "R45") (pin "1") (pinfunction "1_1") (pintype "passive"))
      (node (ref "U6") (pin "64") (pinfunction "M_TXD0_64") (pintype "output"))
      (node (ref "U8") (pin "19") (pinfunction "TX_A_19") (pintype "passive"))
    )
    (net (code "55") (name "/M_TXDN0") (class "Default")
      (node (ref "R44") (pin "1") (pinfunction "1_1") (pintype "passive"))
      (node (ref "U6") (pin "70") (pinfunction "M_TXDN0_70") (pintype "output"))
      (node (ref "U8") (pin "20") (pinfunction "~TX_A_20") (pintype "passive"))
    )
    (net (code "56") (name "/RXD1") (class "Default")
      (node (ref "JP1_X") (pin "9") (pinfunction "9_9") (pintype "passive"))
      (node (ref "U6") (pin "31") (pinfunction "P2.4/T2RST/RXD1/HSI.2_31") (pintype "input"))
    )
    (net (code "57") (name "/TXD1") (class "Default")
      (node (ref "JP1_X") (pin "4") (pinfunction "4_4") (pintype "passive"))
      (node (ref "U6") (pin "36") (pinfunction "P2.6/T2UPDN/TXD1_36") (pintype "bidirectional"))
    )
    (net (code "58") (name "/Temp_1") (class "Default")
      (node (ref "C45") (pin "1") (pinfunction "1_1") (pintype "passive"))
      (node (ref "R32") (pin "1") (pinfunction "1_1") (pintype "passive"))
      (node (ref "R36") (pin "2") (pinfunction "2_2") (pintype "passive"))
      (node (ref "U6") (pin "6") (pinfunction "P0.2/ACH2_6") (pintype "input"))
    )
    (net (code "59") (name "/Unlock") (class "Default")
      (node (ref "P2_X") (pin "9") (pinfunction "9_9") (pintype "passive"))
      (node (ref "R34") (pin "2") (pinfunction "2_2") (pintype "passive"))
      (node (ref "R35") (pin "2") (pinfunction "2_2") (pintype "passive"))
    )
    (net (code "60") (name "/Unlock_MK") (class "Default")
      (node (ref "P5_X") (pin "9") (pinfunction "9_9") (pintype "passive"))
      (node (ref "U6") (pin "19") (pinfunction "P1.3/SPW_DOUT_19") (pintype "bidirectional"))
    )
    (net (code "61") (name "/V_mid_MK") (class "Default")
      (node (ref "P5_X") (pin "1") (pinfunction "1_1") (pintype "passive"))
      (node (ref "U6") (pin "8") (pinfunction "P0.7/ACH7/EXTINT/VMID_8") (pintype "input"))
    )
    (net (code "62") (name "/V_mid_OA") (class "Default")
      (node (ref "C47") (pin "2") (pinfunction "2_2") (pintype "passive"))
      (node (ref "C48") (pin "1") (pinfunction "1_1") (pintype "passive"))
      (node (ref "P2_X") (pin "1") (pinfunction "1_1") (pintype "passive"))
      (node (ref "U2_X") (pin "9") (pinfunction "REF_9") (pintype "input"))
    )
    (net (code "63") (name "/~RD") (class "Default")
      (node (ref "U4") (pin "58") (pinfunction "OE_58") (pintype "input"))
      (node (ref "U6") (pin "68") (pinfunction "~{RD}_68") (pintype "output"))
    )
    (net (code "64") (name "/~RST") (class "Default")
      (node (ref "C26") (pin "1") (pinfunction "1_1") (pintype "passive"))
      (node (ref "JP1_X") (pin "5") (pinfunction "5_5") (pintype "passive"))
      (node (ref "U6") (pin "15") (pinfunction "~{RESET}_15") (pintype "bidirectional"))
    )
    (net (code "65") (name "/~WR") (class "Default")
      (node (ref "P3_X") (pin "1") (pinfunction "1_1") (pintype "passive"))
      (node (ref "R22") (pin "2") (pinfunction "2_2") (pintype "passive"))
      (node (ref "U4") (pin "63") (pinfunction "WE_63") (pintype "input"))
    )
    (net (code "72") (name "3V3") (class "Default")
      (node (ref "C14") (pin "2") (pinfunction "2_2") (pintype "passive"))
      (node (ref "C16") (pin "2") (pinfunction "2_2") (pintype "passive"))
      (node (ref "C17") (pin "2") (pinfunction "2_2") (pintype "passive"))
      (node (ref "C18") (pin "2") (pinfunction "2_2") (pintype "passive"))
      (node (ref "C19") (pin "2") (pinfunction "2_2") (pintype "passive"))
      (node (ref "C20") (pin "2") (pinfunction "2_2") (pintype "passive"))
      (node (ref "C21") (pin "1") (pinfunction "1_1") (pintype "passive"))
      (node (ref "C23") (pin "1") (pinfunction "1_1") (pintype "passive"))
      (node (ref "C33") (pin "2") (pinfunction "2_2") (pintype "passive"))
      (node (ref "C34") (pin "2") (pinfunction "2_2") (pintype "passive"))
      (node (ref "C35") (pin "2") (pinfunction "2_2") (pintype "passive"))
      (node (ref "C36") (pin "2") (pinfunction "2_2") (pintype "passive"))
      (node (ref "C37") (pin "2") (pinfunction "2_2") (pintype "passive"))
      (node (ref "L1") (pin "1") (pinfunction "1_1") (pintype "passive"))
      (node (ref "P3_X") (pin "2") (pinfunction "2_2") (pintype "passive"))
      (node (ref "P8_X") (pin "3") (pinfunction "3_3") (pintype "passive"))
      (node (ref "R13") (pin "1") (pinfunction "1_1") (pintype "passive"))
      (node (ref "R24") (pin "1") (pinfunction "1_1") (pintype "passive"))
      (node (ref "R32") (pin "2") (pinfunction "2_2") (pintype "passive"))
      (node (ref "U4") (pin "1") (pinfunction "VDD_1") (pintype "power_in"))
      (node (ref "U4") (pin "16") (pinfunction "VDD_16") (pintype "power_in"))
      (node (ref "U4") (pin "17") (pinfunction "VDD_17") (pintype "power_in"))
      (node (ref "U4") (pin "27") (pinfunction "VDD_27") (pintype "power_in"))
      (node (ref "U4") (pin "33") (pinfunction "VDD_33") (pintype "power_in"))
      (node (ref "U4") (pin "40") (pinfunction "VDD_40") (pintype "power_in"))
      (node (ref "U4") (pin "52") (pinfunction "VDD_52") (pintype "power_in"))
      (node (ref "U5") (pin "20") (pinfunction "Vcc_20") (pintype "passive"))
      (node (ref "U6") (pin "11") (pinfunction "VCC_11") (pintype "power_in"))
      (node (ref "U6") (pin "33") (pinfunction "VCC_33") (pintype "power_in"))
      (node (ref "U6") (pin "56") (pinfunction "VCC_56") (pintype "power_in"))
      (node (ref "U6") (pin "60") (pinfunction "VCC_60") (pintype "power_in"))
      (node (ref "U6") (pin "78") (pinfunction "VCC_78") (pintype "power_in"))
      (node (ref "U7") (pin "11") (pinfunction "VOUTsens_11") (pintype "passive"))
      (node (ref "U7") (pin "8") (pinfunction "VOUT_8") (pintype "passive"))
    )
    (net (code "73") (name "3V3A") (class "Default")
      (node (ref "C15") (pin "2") (pinfunction "2_2") (pintype "passive"))
      (node (ref "L1") (pin "2") (pinfunction "2_2") (pintype "passive"))
      (node (ref "R12") (pin "1") (pinfunction "1_1") (pintype "passive"))
      (node (ref "U6") (pin "86") (pinfunction "VCCA_86") (pintype "power_in"))
    )
    (net (code "74") (name "GND") (class "Default")
      (node (ref "C10") (pin "2") (pinfunction "2_2") (pintype "passive"))
      (node (ref "C11") (pin "1") (pinfunction "1_1") (pintype "passive"))
      (node (ref "C12") (pin "1") (pinfunction "1_1") (pintype "passive"))
      (node (ref "C13") (pin "1") (pinfunction "1_1") (pintype "passive"))
      (node (ref "C14") (pin "1") (pinfunction "1_1") (pintype "passive"))
      (node (ref "C15") (pin "1") (pinfunction "1_1") (pintype "passive"))
      (node (ref "C16") (pin "1") (pinfunction "1_1") (pintype "passive"))
      (node (ref "C17") (pin "1") (pinfunction "1_1") (pintype "passive"))
      (node (ref "C18") (pin "1") (pinfunction "1_1") (pintype "passive"))
      (node (ref "C19") (pin "1") (pinfunction "1_1") (pintype "passive"))
      (node (ref "C20") (pin "1") (pinfunction "1_1") (pintype "passive"))
      (node (ref "C21") (pin "2") (pinfunction "2_2") (pintype "passive"))
      (node (ref "C22") (pin "2") (pinfunction "2_2") (pintype "passive"))
      (node (ref "C23") (pin "2") (pinfunction "2_2") (pintype "passive"))
      (node (ref "C24") (pin "2") (pinfunction "2_2") (pintype "passive"))
      (node (ref "C25") (pin "2") (pinfunction "2_2") (pintype "passive"))
      (node (ref "C26") (pin "2") (pinfunction "2_2") (pintype "passive"))
      (node (ref "C33") (pin "1") (pinfunction "1_1") (pintype "passive"))
      (node (ref "C34") (pin "1") (pinfunction "1_1") (pintype "passive"))
      (node (ref "C35") (pin "1") (pinfunction "1_1") (pintype "passive"))
      (node (ref "C36") (pin "1") (pinfunction "1_1") (pintype "passive"))
      (node (ref "C37") (pin "1") (pinfunction "1_1") (pintype "passive"))
      (node (ref "C38") (pin "1") (pinfunction "1_1") (pintype "passive"))
      (node (ref "C39") (pin "1") (pinfunction "1_1") (pintype "passive"))
      (node (ref "C40") (pin "2") (pinfunction "2_2") (pintype "passive"))
      (node (ref "C41") (pin "2") (pinfunction "2_2") (pintype "passive"))
      (node (ref "C42") (pin "2") (pinfunction "2_2") (pintype "passive"))
      (node (ref "C43") (pin "1") (pinfunction "1_1") (pintype "passive"))
      (node (ref "C44") (pin "1") (pinfunction "1_1") (pintype "passive"))
      (node (ref "C45") (pin "2") (pinfunction "2_2") (pintype "passive"))
      (node (ref "C47") (pin "1") (pinfunction "1_1") (pintype "passive"))
      (node (ref "C48") (pin "2") (pinfunction "2_2") (pintype "passive"))
      (node (ref "C7") (pin "2") (pinfunction "2_2") (pintype "passive"))
      (node (ref "C8") (pin "1") (pinfunction "1_1") (pintype "passive"))
      (node (ref "C9") (pin "2") (pinfunction "2_2") (pintype "passive"))
      (node (ref "JP1_X") (pin "10") (pinfunction "10_10") (pintype "passive"))
      (node (ref "JP1_X") (pin "2") (pinfunction "2_2") (pintype "passive"))
      (node (ref "L2") (pin "1") (pinfunction "1_1") (pintype "passive"))
      (node (ref "P2_X") (pin "2") (pinfunction "2_2") (pintype "passive"))
      (node (ref "P4_X") (pin "5") (pinfunction "5_5") (pintype "passive"))
      (node (ref "P4_X") (pin "6") (pinfunction "6_6") (pintype "passive"))
      (node (ref "P4_X") (pin "7") (pinfunction "7_7") (pintype "passive"))
      (node (ref "P4_X") (pin "8") (pinfunction "8_8") (pintype "passive"))
      (node (ref "P5_X") (pin "2") (pinfunction "2_2") (pintype "passive"))
      (node (ref "P6_X") (pin "5") (pinfunction "5_5") (pintype "passive"))
      (node (ref "P6_X") (pin "6") (pinfunction "6_6") (pintype "passive"))
      (node (ref "P6_X") (pin "7") (pinfunction "7_7") (pintype "passive"))
      (node (ref "P6_X") (pin "8") (pinfunction "8_8") (pintype "passive"))
      (node (ref "P7_X") (pin "5") (pinfunction "5_5") (pintype "passive"))
      (node (ref "P7_X") (pin "6") (pinfunction "6_6") (pintype "passive"))
      (node (ref "P7_X") (pin "7") (pinfunction "7_7") (pintype "passive"))
      (node (ref "P7_X") (pin "8") (pinfunction "8_8") (pintype "passive"))
      (node (ref "R16") (pin "1") (pinfunction "1_1") (pintype "passive"))
      (node (ref "R17") (pin "2") (pinfunction "2_2") (pintype "passive"))
      (node (ref "R2") (pin "1") (pinfunction "1_1") (pintype "passive"))
      (node (ref "R33") (pin "1") (pinfunction "1_1") (pintype "passive"))
      (node (ref "R36") (pin "1") (pinfunction "1_1") (pintype "passive"))
      (node (ref "R4") (pin "1") (pinfunction "1_1") (pintype "passive"))
      (node (ref "R40") (pin "2") (pinfunction "2_2") (pintype "passive"))
      (node (ref "R44") (pin "2") (pinfunction "2_2") (pintype "passive"))
      (node (ref "R45") (pin "2") (pinfunction "2_2") (pintype "passive"))
      (node (ref "RL1") (pin "1") (pintype "passive"))
      (node (ref "T1") (pin "2") (pinfunction "2,3_2") (pintype "passive"))
      (node (ref "T1") (pin "3") (pinfunction "3_3") (pintype "passive"))
      (node (ref "U2") (pin "2") (pinfunction "GRD_2") (pintype "passive"))
      (node (ref "U2") (pin "7") (pinfunction "GRD_7") (pintype "passive"))
      (node (ref "U2_X") (pin "10") (pinfunction "+IN_10") (pintype "input"))
      (node (ref "U2_X") (pin "2") (pinfunction "DGND_2") (pintype "power_in"))
      (node (ref "U4") (pin "15") (pinfunction "VSS_15") (pintype "power_in"))
      (node (ref "U4") (pin "28") (pinfunction "VSS_28") (pintype "power_in"))
      (node (ref "U4") (pin "32") (pinfunction "VSS_32") (pintype "power_in"))
      (node (ref "U4") (pin "39") (pinfunction "VSS_39") (pintype "power_in"))
      (node (ref "U4") (pin "44") (pinfunction "CE_44") (pintype "input"))
      (node (ref "U4") (pin "50") (pinfunction "VSS_50") (pintype "power_in"))
      (node (ref "U4") (pin "51") (pinfunction "VSS_51") (pintype "power_in"))
      (node (ref "U5") (pin "1") (pinfunction "~ENA_1") (pintype "passive"))
      (node (ref "U5") (pin "10") (pinfunction "GND_10") (pintype "passive"))
      (node (ref "U6") (pin "12") (pinfunction "GND_12") (pintype "power_in"))
      (node (ref "U6") (pin "3") (pinfunction "GNDA_3") (pintype "power_in"))
      (node (ref "U6") (pin "34") (pinfunction "GND_34") (pintype "power_in"))
      (node (ref "U6") (pin "43") (pinfunction "READY_43") (pintype "input"))
      (node (ref "U6") (pin "53") (pinfunction "GND_53") (pintype "power_in"))
      (node (ref "U6") (pin "55") (pinfunction "GND_55") (pintype "power_in"))
      (node (ref "U6") (pin "57") (pinfunction "GND_57") (pintype "power_in"))
      (node (ref "U6") (pin "71") (pinfunction "BW_71") (pintype "input"))
      (node (ref "U6") (pin "75") (pinfunction "NMI_75") (pintype "input"))
      (node (ref "U6") (pin "76") (pinfunction "~{EA}_76") (pintype "input"))
      (node (ref "U6") (pin "77") (pinfunction "GND_77") (pintype "power_in"))
      (node (ref "U8") (pin "10") (pinfunction "GND_B_10") (pintype "passive"))
      (node (ref "U8") (pin "18") (pinfunction "TXINH_A_18") (pintype "passive"))
      (node (ref "U8") (pin "5") (pinfunction "GND_A_5") (pintype "passive"))
      (node (ref "VT2") (pin "1") (pinfunction "EMMITOR_1") (pintype "passive"))
    )
    (net (code "75") (name "GND_pwr") (class "Default")
      (node (ref "C1") (pin "1") (pinfunction "1_1") (pintype "passive"))
      (node (ref "C2") (pin "2") (pinfunction "2_2") (pintype "passive"))
      (node (ref "C27") (pin "1") (pinfunction "1_1") (pintype "passive"))
      (node (ref "C28") (pin "2") (pinfunction "2_2") (pintype "passive"))
      (node (ref "C29") (pin "2") (pinfunction "2_2") (pintype "passive"))
      (node (ref "C3") (pin "2") (pinfunction "2_2") (pintype "passive"))
      (node (ref "C32") (pin "1") (pinfunction "1_1") (pintype "passive"))
      (node (ref "C4") (pin "1") (pinfunction "1_1") (pintype "passive"))
      (node (ref "C46") (pin "2") (pinfunction "2_2") (pintype "passive"))
      (node (ref "L2") (pin "2") (pinfunction "2_2") (pintype "passive"))
      (node (ref "R26") (pin "1") (pinfunction "1_1") (pintype "passive"))
      (node (ref "R38") (pin "1") (pinfunction "1_1") (pintype "passive"))
      (node (ref "U1") (pin "4") (pinfunction "VCOMM_4") (pintype "passive"))
      (node (ref "U1") (pin "5") (pinfunction "C_GND_5") (pintype "passive"))
      (node (ref "VT3") (pin "1") (pinfunction "EMMITOR_1") (pintype "passive"))
    )
    (net (code "76") (name "Net-(C29-Pad1)") (class "Default")
      (node (ref "C29") (pin "1") (pinfunction "1_1") (pintype "passive"))
      (node (ref "C30") (pin "1") (pinfunction "1_1") (pintype "passive"))
      (node (ref "R21") (pin "2") (pinfunction "2_2") (pintype "passive"))
      (node (ref "T2") (pin "2") (pinfunction "2_2") (pintype "passive"))
    )
    (net (code "77") (name "Net-(C30-Pad2)") (class "Default")
      (node (ref "C30") (pin "2") (pinfunction "2_2") (pintype "passive"))
      (node (ref "R23") (pin "1") (pinfunction "1_1") (pintype "passive"))
    )
    (net (code "78") (name "Net-(C44-Pad2)") (class "Default")
      (node (ref "C44") (pin "2") (pinfunction "2_2") (pintype "passive"))
      (node (ref "R7") (pin "1") (pinfunction "1_1") (pintype "passive"))
      (node (ref "R8") (pin "1") (pinfunction "1_1") (pintype "passive"))
    )
    (net (code "79") (name "Net-(L3-Pad1)") (class "Default")
      (node (ref "L3") (pin "1") (pinfunction "1_1") (pintype "passive"))
      (node (ref "P8_X") (pin "2") (pinfunction "2_2") (pintype "passive"))
    )
    (net (code "80") (name "Net-(R5-Pad1)") (class "Default")
      (node (ref "R5") (pin "1") (pinfunction "1_1") (pintype "passive"))
      (node (ref "T1") (pin "5") (pinfunction "5_5") (pintype "passive"))
    )
    (net (code "81") (name "Net-(R7-Pad2)") (class "Default")
      (node (ref "R7") (pin "2") (pinfunction "2_2") (pintype "passive"))
      (node (ref "RL1") (pin "3") (pinfunction "3_3") (pintype "passive"))
    )
    (net (code "82") (name "Net-(R14-Pad2)") (class "Default")
      (node (ref "R14") (pin "2") (pinfunction "2_2") (pintype "passive"))
      (node (ref "R15") (pin "1") (pinfunction "1_1") (pintype "passive"))
    )
    (net (code "83") (name "Net-(R18-Pad2)") (class "Default")
      (node (ref "R18") (pin "2") (pinfunction "2_2") (pintype "passive"))
      (node (ref "R19") (pin "1") (pinfunction "1_1") (pintype "passive"))
    )
    (net (code "84") (name "Net-(R30-Pad1)") (class "Default")
      (node (ref "R30") (pin "1") (pinfunction "1_1") (pintype "passive"))
      (node (ref "T1") (pin "8") (pinfunction "8_8") (pintype "passive"))
    )
    (net (code "85") (name "Net-(R31-Pad1)") (class "Default")
      (node (ref "R31") (pin "1") (pinfunction "1_1") (pintype "passive"))
      (node (ref "RL1") (pin "B") (pintype "passive"))
    )
    (net (code "86") (name "Net-(R37-Pad2)") (class "Default")
      (node (ref "R37") (pin "2") (pinfunction "2_2") (pintype "passive"))
      (node (ref "T2") (pin "4") (pinfunction "4_4") (pintype "passive"))
    )
    (net (code "87") (name "Net-(R38-Pad2)") (class "Default")
      (node (ref "R38") (pin "2") (pinfunction "2_2") (pintype "passive"))
      (node (ref "T2") (pin "1") (pinfunction "1_1") (pintype "passive"))
    )
    (net (code "88") (name "Net-(U1-VIN+)") (class "Default")
      (node (ref "C6") (pin "1") (pinfunction "1_1") (pintype "passive"))
      (node (ref "U1") (pin "1") (pinfunction "VIN+_1") (pintype "passive"))
      (node (ref "U9") (pin "8") (pintype "passive"))
    )
    (net (code "89") (name "Net-(U2-IN+)") (class "Default")
      (node (ref "R40") (pin "1") (pinfunction "1_1") (pintype "passive"))
      (node (ref "U2") (pin "1") (pinfunction "IN+_1") (pintype "input"))
    )
    (net (code "90") (name "Net-(U2-IN-)") (class "Default")
      (node (ref "C5") (pin "2") (pinfunction "2_2") (pintype "passive"))
      (node (ref "R3") (pin "1") (pinfunction "1_1") (pintype "passive"))
      (node (ref "R8") (pin "2") (pinfunction "2_2") (pintype "passive"))
      (node (ref "U2") (pin "8") (pinfunction "IN-_8") (pintype "input"))
    )
    (net (code "91") (name "Net-(U2-OUT)") (class "Default")
      (node (ref "C5") (pin "1") (pinfunction "1_1") (pintype "passive"))
      (node (ref "R3") (pin "2") (pinfunction "2_2") (pintype "passive"))
      (node (ref "R39") (pin "2") (pinfunction "2_2") (pintype "passive"))
      (node (ref "U2") (pin "6") (pinfunction "OUT_6") (pintype "output"))
    )
    (net (code "92") (name "Net-(U2_X--IN)") (class "Default")
      (node (ref "C43") (pin "2") (pinfunction "2_2") (pintype "passive"))
      (node (ref "R39") (pin "1") (pinfunction "1_1") (pintype "passive"))
      (node (ref "U2_X") (pin "1") (pinfunction "-IN_1") (pintype "input"))
    )
    (net (code "93") (name "Net-(U6-P0.4{slash}ACH4)") (class "Default")
      (node (ref "C39") (pin "2") (pinfunction "2_2") (pintype "passive"))
      (node (ref "R28") (pin "2") (pinfunction "2_2") (pintype "passive"))
      (node (ref "U6") (pin "1") (pinfunction "P0.4/ACH4_1") (pintype "input"))
    )
    (net (code "94") (name "Net-(U6-P5.4{slash}ACH12)") (class "Default")
      (node (ref "C40") (pin "1") (pinfunction "1_1") (pintype "passive"))
      (node (ref "R29") (pin "2") (pinfunction "2_2") (pintype "passive"))
      (node (ref "U6") (pin "2") (pinfunction "P5.4/ACH12_2") (pintype "input"))
    )
    (net (code "95") (name "Net-(U6-VPR)") (class "Default")
      (node (ref "R24") (pin "2") (pinfunction "2_2") (pintype "passive"))
      (node (ref "R33") (pin "2") (pinfunction "2_2") (pintype "passive"))
      (node (ref "U6") (pin "38") (pinfunction "VPR_38") (pintype "input"))
    )
    (net (code "96") (name "Net-(U6-XTAL1)") (class "Default")
      (node (ref "C12") (pin "2") (pinfunction "2_2") (pintype "passive"))
      (node (ref "Q1") (pin "1") (pinfunction "1_1") (pintype "passive"))
      (node (ref "R11") (pin "2") (pinfunction "2_2") (pintype "passive"))
      (node (ref "U6") (pin "74") (pinfunction "XTAL1_74") (pintype "input"))
    )
    (net (code "97") (name "Net-(U6-XTAL2)") (class "Default")
      (node (ref "C13") (pin "2") (pinfunction "2_2") (pintype "passive"))
      (node (ref "Q1") (pin "2") (pinfunction "2_2") (pintype "passive"))
      (node (ref "R11") (pin "1") (pinfunction "1_1") (pintype "passive"))
      (node (ref "U6") (pin "73") (pinfunction "XTAL2_73") (pintype "output"))
    )
    (net (code "98") (name "Net-(U6-~{WR}{slash}~{WRL})") (class "Default")
      (node (ref "R22") (pin "1") (pinfunction "1_1") (pintype "passive"))
      (node (ref "U6") (pin "40") (pinfunction "~{WR}/~{WRL}_40") (pintype "output"))
    )
    (net (code "99") (name "Net-(U7-ADJ)") (class "Default")
      (node (ref "R13") (pin "2") (pinfunction "2_2") (pintype "passive"))
      (node (ref "R16") (pin "2") (pinfunction "2_2") (pintype "passive"))
      (node (ref "U7") (pin "17") (pinfunction "ADJ_17") (pintype "passive"))
    )
    (net (code "100") (name "Net-(U8-BUS_A)") (class "Default")
      (node (ref "R43") (pin "1") (pinfunction "1_1") (pintype "passive"))
      (node (ref "R46") (pin "1") (pinfunction "1_1") (pintype "passive"))
      (node (ref "U8") (pin "2") (pinfunction "BUS_A_2") (pintype "passive"))
    )
    (net (code "101") (name "Net-(U8-RXEN_A)") (class "Default")
      (node (ref "R1") (pin "1") (pinfunction "1_1") (pintype "passive"))
      (node (ref "U8") (pin "4") (pinfunction "RXEN_A_4") (pintype "passive"))
    )
    (net (code "102") (name "Net-(U8-RX_A)") (class "Default")
      (node (ref "R9") (pin "2") (pinfunction "2_2") (pintype "passive"))
      (node (ref "U8") (pin "17") (pinfunction "RX_A_17") (pintype "passive"))
    )
    (net (code "103") (name "Net-(U8-~BUS_A)") (class "Default")
      (node (ref "R41") (pin "1") (pinfunction "1_1") (pintype "passive"))
      (node (ref "R42") (pin "1") (pinfunction "1_1") (pintype "passive"))
      (node (ref "U8") (pin "3") (pinfunction "~BUS_A_3") (pintype "passive"))
    )
    (net (code "104") (name "Net-(U8-~RX_A)") (class "Default")
      (node (ref "R6") (pin "2") (pinfunction "2_2") (pintype "passive"))
      (node (ref "U8") (pin "16") (pinfunction "~RX_A_16") (pintype "passive"))
    )
    (net (code "105") (name "Net-(VD3-A)") (class "Default")
      (node (ref "C32") (pin "2") (pinfunction "2_2") (pintype "passive"))
      (node (ref "R20") (pin "2") (pinfunction "2_2") (pintype "passive"))
      (node (ref "R27") (pin "2") (pinfunction "2_2") (pintype "passive"))
      (node (ref "VD3") (pin "1") (pinfunction "A_1") (pintype "passive"))
    )
    (net (code "106") (name "Net-(VD3-K)") (class "Default")
      (node (ref "R37") (pin "1") (pinfunction "1_1") (pintype "passive"))
      (node (ref "VD3") (pin "2") (pinfunction "K_2") (pintype "passive"))
    )
    (net (code "107") (name "Net-(VT2-BASE)") (class "Default")
      (node (ref "R34") (pin "1") (pinfunction "1_1") (pintype "passive"))
      (node (ref "VT2") (pin "2") (pinfunction "BASE_2") (pintype "passive"))
    )
    (net (code "108") (name "Net-(VT2-KOLLECTOR)") (class "Default")
      (node (ref "R31") (pin "2") (pinfunction "2_2") (pintype "passive"))
      (node (ref "VT2") (pin "3") (pinfunction "KOLLECTOR_3") (pintype "passive"))
    )
    (net (code "109") (name "Net-(VT3-BASE)") (class "Default")
      (node (ref "C31") (pin "1") (pinfunction "1_1") (pintype "passive"))
      (node (ref "R25") (pin "2") (pinfunction "2_2") (pintype "passive"))
      (node (ref "R26") (pin "2") (pinfunction "2_2") (pintype "passive"))
      (node (ref "VT3") (pin "2") (pinfunction "BASE_2") (pintype "passive"))
    )
    (net (code "110") (name "Net-(VT3-KOLLECTOR)") (class "Default")
      (node (ref "R23") (pin "2") (pinfunction "2_2") (pintype "passive"))
      (node (ref "T2") (pin "3") (pinfunction "3_3") (pintype "passive"))
      (node (ref "VT3") (pin "3") (pinfunction "KOLLECTOR_3") (pintype "passive"))
    )
    (net (code "111") (name "Vcc") (class "Default")
      (node (ref "C38") (pin "2") (pinfunction "2_2") (pintype "passive"))
      (node (ref "C42") (pin "1") (pinfunction "1_1") (pintype "passive"))
      (node (ref "C8") (pin "2") (pinfunction "2_2") (pintype "passive"))
      (node (ref "L3") (pin "2") (pinfunction "2_2") (pintype "passive"))
      (node (ref "R1") (pin "2") (pinfunction "2_2") (pintype "passive"))
      (node (ref "U8") (pin "1") (pinfunction "Vcc_A_1") (pintype "passive"))
    )
    (net (code "112") (name "unconnected-(JP1_X-Pad1)") (class "Default")
      (node (ref "JP1_X") (pin "1") (pinfunction "1_1") (pintype "passive"))
    )
    (net (code "113") (name "unconnected-(JP1_X-Pad3)") (class "Default")
      (node (ref "JP1_X") (pin "3") (pinfunction "3_3") (pintype "passive"))
    )
    (net (code "114") (name "unconnected-(JP1_X-Pad6)") (class "Default")
      (node (ref "JP1_X") (pin "6") (pinfunction "6_6") (pintype "passive"))
    )
    (net (code "115") (name "unconnected-(JP1_X-Pad7)") (class "Default")
      (node (ref "JP1_X") (pin "7") (pinfunction "7_7") (pintype "passive"))
    )
    (net (code "116") (name "unconnected-(JP1_X-Pad8)") (class "Default")
      (node (ref "JP1_X") (pin "8") (pinfunction "8_8") (pintype "passive"))
    )
    (net (code "117") (name "unconnected-(P1-MH1-Pad16)") (class "Default")
      (node (ref "P1") (pin "16") (pinfunction "MH1_16") (pintype "passive"))
    )
    (net (code "118") (name "unconnected-(P1-MH2-Pad17)") (class "Default")
      (node (ref "P1") (pin "17") (pinfunction "MH2_17") (pintype "passive"))
    )
    (net (code "119") (name "unconnected-(P1-Pad3)") (class "Default")
      (node (ref "P1") (pin "3") (pinfunction "3_3") (pintype "passive"))
    )
    (net (code "120") (name "unconnected-(P1-Pad5)") (class "Default")
      (node (ref "P1") (pin "5") (pinfunction "5_5") (pintype "passive"))
    )
    (net (code "121") (name "unconnected-(P1-Pad6)") (class "Default")
      (node (ref "P1") (pin "6") (pinfunction "6_6") (pintype "passive"))
    )
    (net (code "122") (name "unconnected-(P1-Pad11)") (class "Default")
      (node (ref "P1") (pin "11") (pinfunction "11_11") (pintype "passive"))
    )
    (net (code "123") (name "unconnected-(P1-Pad13)") (class "Default")
      (node (ref "P1") (pin "13") (pinfunction "13_13") (pintype "passive"))
    )
    (net (code "124") (name "unconnected-(T1-Pad6)") (class "Default")
      (node (ref "T1") (pin "6") (pinfunction "6_6") (pintype "passive"))
    )
    (net (code "125") (name "unconnected-(T1-Pad7)") (class "Default")
      (node (ref "T1") (pin "7") (pinfunction "7_7") (pintype "passive"))
    )
    (net (code "126") (name "unconnected-(U1-INH-Pad7)") (class "Default")
      (node (ref "U1") (pin "7") (pinfunction "INH_7") (pintype "passive"))
    )
    (net (code "127") (name "unconnected-(U4-H_VDD-Pad48)") (class "Default")
      (node (ref "U4") (pin "48") (pinfunction "H_VDD_48") (pintype "power_in"))
    )
    (net (code "128") (name "unconnected-(U4-VSS-Pad64)") (class "Default")
      (node (ref "U4") (pin "64") (pinfunction "VSS_64") (pintype "power_in"))
    )
    (net (code "129") (name "unconnected-(U6-AD15-Pad45)") (class "Default")
      (node (ref "U6") (pin "45") (pinfunction "AD15_45") (pintype "tri_state"))
    )
    (net (code "130") (name "unconnected-(U6-CLKOUT-Pad72)") (class "Default")
      (node (ref "U6") (pin "72") (pinfunction "CLKOUT_72") (pintype "output"))
    )
    (net (code "131") (name "unconnected-(U6-HSO.3-Pad39)") (class "Default")
      (node (ref "U6") (pin "39") (pinfunction "HSO.3_39") (pintype "output"))
    )
    (net (code "132") (name "unconnected-(U6-INST-Pad79)") (class "Default")
      (node (ref "U6") (pin "79") (pinfunction "INST_79") (pintype "output+no_connect"))
    )
    (net (code "133") (name "unconnected-(U6-M_RXD1-Pad30)") (class "Default")
      (node (ref "U6") (pin "30") (pinfunction "M_RXD1_30") (pintype "input+no_connect"))
    )
    (net (code "134") (name "unconnected-(U6-M_RXDN1-Pad25)") (class "Default")
      (node (ref "U6") (pin "25") (pinfunction "M_RXDN1_25") (pintype "input+no_connect"))
    )
    (net (code "135") (name "unconnected-(U6-M_TXD1-Pad54)") (class "Default")
      (node (ref "U6") (pin "54") (pinfunction "M_TXD1_54") (pintype "output"))
    )
    (net (code "136") (name "unconnected-(U6-M_TXDN1-Pad44)") (class "Default")
      (node (ref "U6") (pin "44") (pinfunction "M_TXDN1_44") (pintype "output"))
    )
    (net (code "137") (name "unconnected-(U6-P0.0{slash}ACH0-Pad80)") (class "Default")
      (node (ref "U6") (pin "80") (pinfunction "P0.0/ACH0_80") (pintype "input+no_connect"))
    )
    (net (code "138") (name "unconnected-(U6-P0.1{slash}ACH1-Pad82)") (class "Default")
      (node (ref "U6") (pin "82") (pinfunction "P0.1/ACH1_82") (pintype "input+no_connect"))
    )
    (net (code "139") (name "unconnected-(U6-P0.3{slash}ACH3-Pad87)") (class "Default")
      (node (ref "U6") (pin "87") (pinfunction "P0.3/ACH3_87") (pintype "input+no_connect"))
    )
    (net (code "140") (name "unconnected-(U6-P0.5{slash}ACH5-Pad4)") (class "Default")
      (node (ref "U6") (pin "4") (pinfunction "P0.5/ACH5_4") (pintype "input+no_connect"))
    )
    (net (code "141") (name "unconnected-(U6-P0.6{slash}ACH6-Pad84)") (class "Default")
      (node (ref "U6") (pin "84") (pinfunction "P0.6/ACH6_84") (pintype "input+no_connect"))
    )
    (net (code "142") (name "unconnected-(U6-P1.0{slash}SPW_DIN-Pad16)") (class "Default")
      (node (ref "U6") (pin "16") (pinfunction "P1.0/SPW_DIN_16") (pintype "bidirectional"))
    )
    (net (code "143") (name "unconnected-(U6-P1.1{slash}SPW_SIN-Pad17)") (class "Default")
      (node (ref "U6") (pin "17") (pinfunction "P1.1/SPW_SIN_17") (pintype "bidirectional"))
    )
    (net (code "144") (name "unconnected-(U6-P1.2{slash}~{SS}{slash}HSO.0-Pad18)") (class "Default")
      (node (ref "U6") (pin "18") (pinfunction "P1.2/~{SS}/HSO.0_18") (pintype "bidirectional"))
    )
    (net (code "145") (name "unconnected-(U6-P1.6{slash}MISO{slash}HSO.2-Pad23)") (class "Default")
      (node (ref "U6") (pin "23") (pinfunction "P1.6/MISO/HSO.2_23") (pintype "bidirectional"))
    )
    (net (code "146") (name "unconnected-(U6-P1.7{slash}SCK{slash}HSO.4-Pad24)") (class "Default")
      (node (ref "U6") (pin "24") (pinfunction "P1.7/SCK/HSO.4_24") (pintype "bidirectional+no_connect"))
    )
    (net (code "147") (name "unconnected-(U6-P2.0{slash}TXD0-Pad26)") (class "Default")
      (node (ref "U6") (pin "26") (pinfunction "P2.0/TXD0_26") (pintype "output+no_connect"))
    )
    (net (code "148") (name "unconnected-(U6-P2.1{slash}RXD0-Pad27)") (class "Default")
      (node (ref "U6") (pin "27") (pinfunction "P2.1/RXD0_27") (pintype "input+no_connect"))
    )
    (net (code "149") (name "unconnected-(U6-P2.2{slash}EXTINT{slash}HSI.0-Pad28)") (class "Default")
      (node (ref "U6") (pin "28") (pinfunction "P2.2/EXTINT/HSI.0_28") (pintype "input+no_connect"))
    )
    (net (code "150") (name "unconnected-(U6-P2.3{slash}T2CLK{slash}HSI.1{slash}SCL-Pad29)") (class "Default")
      (node (ref "U6") (pin "29") (pinfunction "P2.3/T2CLK/HSI.1/SCL_29") (pintype "input+no_connect"))
    )
    (net (code "151") (name "unconnected-(U6-P2.5{slash}PWM.0{slash}HSO.5-Pad32)") (class "Default")
      (node (ref "U6") (pin "32") (pinfunction "P2.5/PWM.0/HSO.5_32") (pintype "output"))
    )
    (net (code "152") (name "unconnected-(U6-P2.7{slash}T2CAP{slash}HSI.3{slash}SDA-Pad37)") (class "Default")
      (node (ref "U6") (pin "37") (pinfunction "P2.7/T2CAP/HSI.3/SDA_37") (pintype "bidirectional"))
    )
    (net (code "153") (name "unconnected-(U6-P5.0{slash}ACH8-Pad81)") (class "Default")
      (node (ref "U6") (pin "81") (pinfunction "P5.0/ACH8_81") (pintype "input+no_connect"))
    )
    (net (code "154") (name "unconnected-(U6-P5.1{slash}ACH9-Pad83)") (class "Default")
      (node (ref "U6") (pin "83") (pinfunction "P5.1/ACH9_83") (pintype "input+no_connect"))
    )
    (net (code "155") (name "unconnected-(U6-P5.2{slash}ACH10-Pad7)") (class "Default")
      (node (ref "U6") (pin "7") (pinfunction "P5.2/ACH10_7") (pintype "input+no_connect"))
    )
    (net (code "156") (name "unconnected-(U6-P5.3{slash}ACH11-Pad88)") (class "Default")
      (node (ref "U6") (pin "88") (pinfunction "P5.3/ACH11_88") (pintype "input+no_connect"))
    )
    (net (code "157") (name "unconnected-(U6-P5.5{slash}ACH13-Pad5)") (class "Default")
      (node (ref "U6") (pin "5") (pinfunction "P5.5/ACH13_5") (pintype "input+no_connect"))
    )
    (net (code "158") (name "unconnected-(U6-P5.6{slash}ACH14-Pad85)") (class "Default")
      (node (ref "U6") (pin "85") (pinfunction "P5.6/ACH14_85") (pintype "input+no_connect"))
    )
    (net (code "159") (name "unconnected-(U6-P5.7{slash}ACH15-Pad9)") (class "Default")
      (node (ref "U6") (pin "9") (pinfunction "P5.7/ACH15_9") (pintype "input+no_connect"))
    )
    (net (code "160") (name "unconnected-(U6-PWM.2-Pad14)") (class "Default")
      (node (ref "U6") (pin "14") (pinfunction "PWM.2_14") (pintype "output"))
    )
    (net (code "161") (name "unconnected-(U6-~{BHE}{slash}~{WRH}-Pad42)") (class "Default")
      (node (ref "U6") (pin "42") (pinfunction "~{BHE}/~{WRH}_42") (pintype "output"))
    )
    (net (code "162") (name "unconnected-(U8-BUS_B-Pad7)") (class "Default")
      (node (ref "U8") (pin "7") (pinfunction "BUS_B_7") (pintype "passive"))
    )
    (net (code "163") (name "unconnected-(U8-RXEN_B-Pad9)") (class "Default")
      (node (ref "U8") (pin "9") (pinfunction "RXEN_B_9") (pintype "passive"))
    )
    (net (code "164") (name "unconnected-(U8-RX_B-Pad12)") (class "Default")
      (node (ref "U8") (pin "12") (pinfunction "RX_B_12") (pintype "passive"))
    )
    (net (code "165") (name "unconnected-(U8-TXINH_B-Pad13)") (class "Default")
      (node (ref "U8") (pin "13") (pinfunction "TXINH_B_13") (pintype "passive"))
    )
    (net (code "166") (name "unconnected-(U8-TX_B-Pad14)") (class "Default")
      (node (ref "U8") (pin "14") (pinfunction "TX_B_14") (pintype "passive"))
    )
    (net (code "167") (name "unconnected-(U8-Vcc_B-Pad6)") (class "Default")
      (node (ref "U8") (pin "6") (pinfunction "Vcc_B_6") (pintype "passive"))
    )
    (net (code "168") (name "unconnected-(U8-~BUS_B-Pad8)") (class "Default")
      (node (ref "U8") (pin "8") (pinfunction "~BUS_B_8") (pintype "passive"))
    )
    (net (code "169") (name "unconnected-(U8-~RX_B-Pad11)") (class "Default")
      (node (ref "U8") (pin "11") (pinfunction "~RX_B_11") (pintype "passive"))
    )
    (net (code "170") (name "unconnected-(U8-~TX_B-Pad15)") (class "Default")
      (node (ref "U8") (pin "15") (pinfunction "~TX_B_15") (pintype "passive"))
    )
  )
)
